# FRDM-MCXN947__Shield_Template.net
KiCad netlist of a schematic drawn in Altium Designer
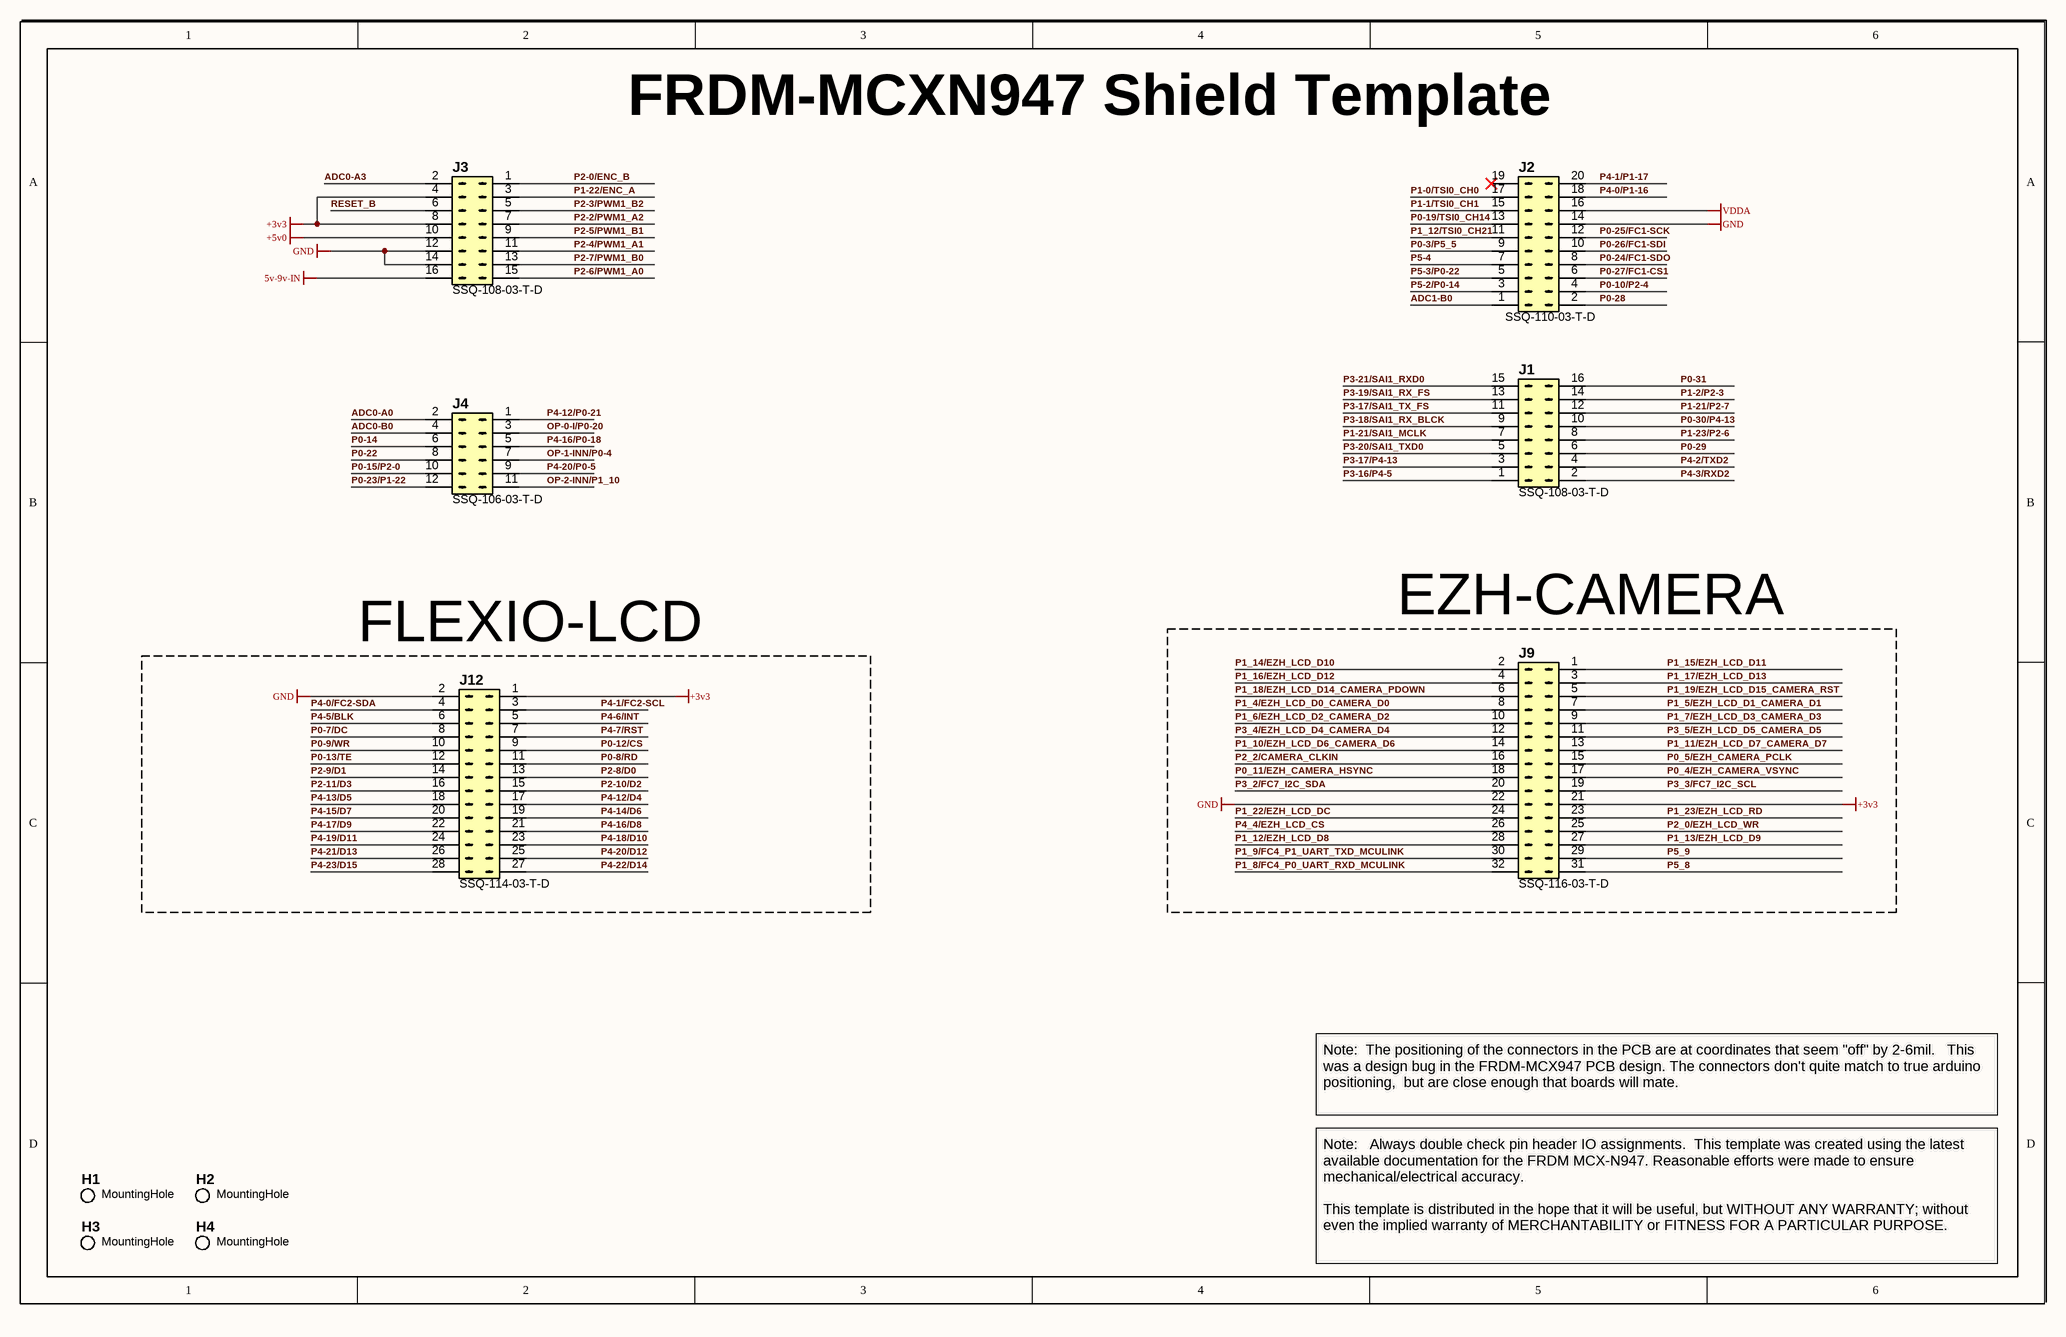
[diagram p0: FRDM-MCXN947__Shield_Template.SchDoc]

(export (version "E")
  (design (tool "Eeschema 10.0.6"))
  (components
    (comp (ref "H1")
      (value "MountingHole")
      (footprint "MountingHole_3.2mm_M3")
      (fields (field (name "Comment") "Mechanical_MountingHole"))
      (libsource (lib "PCB-10012__FRDM-MCXN947__Template__A") (part "Mechanical_MountingHole"))
    )
    (comp (ref "H2")
      (value "MountingHole")
      (footprint "MountingHole_3.2mm_M3")
      (fields (field (name "Comment") "Mechanical_MountingHole"))
      (libsource (lib "PCB-10012__FRDM-MCXN947__Template__A") (part "Mechanical_MountingHole"))
    )
    (comp (ref "H3")
      (value "MountingHole")
      (footprint "MountingHole_3.2mm_M3")
      (fields (field (name "Comment") "Mechanical_MountingHole"))
      (libsource (lib "PCB-10012__FRDM-MCXN947__Template__A") (part "Mechanical_MountingHole"))
    )
    (comp (ref "H4")
      (value "MountingHole")
      (footprint "MountingHole_3.2mm_M3")
      (fields (field (name "Comment") "Mechanical_MountingHole"))
      (libsource (lib "PCB-10012__FRDM-MCXN947__Template__A") (part "Mechanical_MountingHole"))
    )
    (comp (ref "J1")
      (value "SSQ-108-03-T-D")
      (footprint "SSQ-108-03-T-D")
      (fields (field (name "MANUFACTURER") "Samtec Inc."))
      (libsource (lib "") (part "SSQ-108-03-T-D_1"))
    )
    (comp (ref "J2")
      (value "SSQ-110-03-T-D")
      (footprint "SSQ-110-03-T-D")
      (fields
        (field (name "MANUFACTURER") "Samtec Inc.")
        (field (name "MANUFACTURER PART NUMBER") "SSQ-110-23-T-D")
      )
      (libsource (lib "PCB-10012__FRDM-MCXN947__Template__A") (part "SSQ-110-03-T-D"))
    )
    (comp (ref "J3")
      (value "SSQ-108-03-T-D")
      (footprint "SSQ-108-03-T-D")
      (fields (field (name "MANUFACTURER") "Samtec Inc."))
      (libsource (lib "PCB-10012__FRDM-MCXN947__Template__A") (part "SSQ-108-03-T-D"))
    )
    (comp (ref "J4")
      (value "SSQ-106-03-T-D")
      (footprint "SSQ-106-03-T-D")
      (fields (field (name "MANUFACTURER") "Samtec Inc."))
      (libsource (lib "PCB-10012__FRDM-MCXN947__Template__A") (part "SSQ-106-03-T-D"))
    )
    (comp (ref "J9")
      (value "SSQ-116-03-T-D")
      (footprint "SSQ-116-03-T-D")
      (fields (field (name "MANUFACTURER") "Samtec Inc."))
      (libsource (lib "PCB-10012__FRDM-MCXN947__Template__A") (part "SSQ-116-03-T-D"))
    )
    (comp (ref "J12")
      (value "SSQ-114-03-T-D")
      (footprint "SSQ-114-03-T-D")
      (fields (field (name "MANUFACTURER") "Samtec Inc."))
      (libsource (lib "PCB-10012__FRDM-MCXN947__Template__A") (part "SSQ-114-03-T-D"))
    )
  )
  (nets
    (net (code "1") (name "+3v3") (class "Default")
      (node (ref "J12") (pin "1") (pinfunction "Pin_1_1") (pintype "passive"))
      (node (ref "J3") (pin "4") (pinfunction "Pin_4_4") (pintype "passive"))
      (node (ref "J3") (pin "8") (pinfunction "Pin_8_8") (pintype "passive"))
      (node (ref "J9") (pin "21") (pinfunction "Pin_21_21") (pintype "passive"))
    )
    (net (code "2") (name "+5v0") (class "Default")
      (node (ref "J3") (pin "10") (pinfunction "Pin_10_10") (pintype "passive"))
    )
    (net (code "3") (name "/ADC0-A0") (class "Default")
      (node (ref "J4") (pin "2") (pinfunction "Pin_2_2") (pintype "passive"))
    )
    (net (code "4") (name "/ADC0-A3") (class "Default")
      (node (ref "J3") (pin "2") (pinfunction "Pin_2_2") (pintype "passive"))
    )
    (net (code "5") (name "/ADC0-B0") (class "Default")
      (node (ref "J4") (pin "4") (pinfunction "Pin_4_4") (pintype "passive"))
    )
    (net (code "6") (name "/ADC1-B0") (class "Default")
      (node (ref "J2") (pin "1") (pinfunction "Pin_1_1") (pintype "passive"))
    )
    (net (code "7") (name "/OP-0-I{slash}P0-20") (class "Default")
      (node (ref "J4") (pin "3") (pinfunction "Pin_3_3") (pintype "passive"))
    )
    (net (code "8") (name "/OP-1-INN{slash}P0-4") (class "Default")
      (node (ref "J4") (pin "7") (pinfunction "Pin_7_7") (pintype "passive"))
    )
    (net (code "9") (name "/OP-2-INN{slash}P1_10") (class "Default")
      (node (ref "J4") (pin "11") (pinfunction "Pin_11_11") (pintype "passive"))
    )
    (net (code "10") (name "/P0-3{slash}P5_5") (class "Default")
      (node (ref "J2") (pin "9") (pinfunction "Pin_9_9") (pintype "passive"))
    )
    (net (code "11") (name "/P0-7{slash}DC") (class "Default")
      (node (ref "J12") (pin "8") (pinfunction "Pin_8_8") (pintype "passive"))
    )
    (net (code "12") (name "/P0-8{slash}RD") (class "Default")
      (node (ref "J12") (pin "11") (pinfunction "Pin_11_11") (pintype "passive"))
    )
    (net (code "13") (name "/P0-9{slash}WR") (class "Default")
      (node (ref "J12") (pin "10") (pinfunction "Pin_10_10") (pintype "passive"))
    )
    (net (code "14") (name "/P0-10{slash}P2-4") (class "Default")
      (node (ref "J2") (pin "4") (pinfunction "Pin_4_4") (pintype "passive"))
    )
    (net (code "15") (name "/P0-12{slash}CS") (class "Default")
      (node (ref "J12") (pin "9") (pinfunction "Pin_9_9") (pintype "passive"))
    )
    (net (code "16") (name "/P0-13{slash}TE") (class "Default")
      (node (ref "J12") (pin "12") (pinfunction "Pin_12_12") (pintype "passive"))
    )
    (net (code "17") (name "/P0-14") (class "Default")
      (node (ref "J4") (pin "6") (pinfunction "Pin_6_6") (pintype "passive"))
    )
    (net (code "18") (name "/P0-15{slash}P2-0") (class "Default")
      (node (ref "J4") (pin "10") (pinfunction "Pin_10_10") (pintype "passive"))
    )
    (net (code "19") (name "/P0-19{slash}TSI0_CH14") (class "Default")
      (node (ref "J2") (pin "13") (pinfunction "Pin_13_13") (pintype "passive"))
    )
    (net (code "20") (name "/P0-22") (class "Default")
      (node (ref "J4") (pin "8") (pinfunction "Pin_8_8") (pintype "passive"))
    )
    (net (code "21") (name "/P0-23{slash}P1-22") (class "Default")
      (node (ref "J4") (pin "12") (pinfunction "Pin_12_12") (pintype "passive"))
    )
    (net (code "22") (name "/P0-24{slash}FC1-SDO") (class "Default")
      (node (ref "J2") (pin "8") (pinfunction "Pin_8_8") (pintype "passive"))
    )
    (net (code "23") (name "/P0-25{slash}FC1-SCK") (class "Default")
      (node (ref "J2") (pin "12") (pinfunction "Pin_12_12") (pintype "passive"))
    )
    (net (code "24") (name "/P0-26{slash}FC1-SDI") (class "Default")
      (node (ref "J2") (pin "10") (pinfunction "Pin_10_10") (pintype "passive"))
    )
    (net (code "25") (name "/P0-27{slash}FC1-CS1") (class "Default")
      (node (ref "J2") (pin "6") (pinfunction "Pin_6_6") (pintype "passive"))
    )
    (net (code "26") (name "/P0-28") (class "Default")
      (node (ref "J2") (pin "2") (pinfunction "Pin_2_2") (pintype "passive"))
    )
    (net (code "27") (name "/P0-29") (class "Default")
      (node (ref "J1") (pin "6") (pinfunction "Pin_6_6") (pintype "passive"))
    )
    (net (code "28") (name "/P0-30{slash}P4-13") (class "Default")
      (node (ref "J1") (pin "10") (pinfunction "Pin_10_10") (pintype "passive"))
    )
    (net (code "29") (name "/P0-31") (class "Default")
      (node (ref "J1") (pin "16") (pinfunction "Pin_16_16") (pintype "passive"))
    )
    (net (code "30") (name "/P0_4{slash}EZH_CAMERA_VSYNC") (class "Default")
      (node (ref "J9") (pin "17") (pinfunction "Pin_17_17") (pintype "passive"))
    )
    (net (code "31") (name "/P0_5{slash}EZH_CAMERA_PCLK") (class "Default")
      (node (ref "J9") (pin "15") (pinfunction "Pin_15_15") (pintype "passive"))
    )
    (net (code "32") (name "/P0_11{slash}EZH_CAMERA_HSYNC") (class "Default")
      (node (ref "J9") (pin "18") (pinfunction "Pin_18_18") (pintype "passive"))
    )
    (net (code "33") (name "/P1-0{slash}TSI0_CH0") (class "Default")
      (node (ref "J2") (pin "17") (pinfunction "Pin_17_17") (pintype "passive"))
    )
    (net (code "34") (name "/P1-1{slash}TSI0_CH1") (class "Default")
      (node (ref "J2") (pin "15") (pinfunction "Pin_15_15") (pintype "passive"))
    )
    (net (code "35") (name "/P1-2{slash}P2-3") (class "Default")
      (node (ref "J1") (pin "14") (pinfunction "Pin_14_14") (pintype "passive"))
    )
    (net (code "36") (name "/P1-21{slash}P2-7") (class "Default")
      (node (ref "J1") (pin "12") (pinfunction "Pin_12_12") (pintype "passive"))
    )
    (net (code "37") (name "/P1-21{slash}SAI1_MCLK") (class "Default")
      (node (ref "J1") (pin "7") (pinfunction "Pin_7_7") (pintype "passive"))
    )
    (net (code "38") (name "/P1-22{slash}ENC_A") (class "Default")
      (node (ref "J3") (pin "3") (pinfunction "Pin_3_3") (pintype "passive"))
    )
    (net (code "39") (name "/P1-23{slash}P2-6") (class "Default")
      (node (ref "J1") (pin "8") (pinfunction "Pin_8_8") (pintype "passive"))
    )
    (net (code "40") (name "/P1_4{slash}EZH_LCD_D0_CAMERA_D0") (class "Default")
      (node (ref "J9") (pin "8") (pinfunction "Pin_8_8") (pintype "passive"))
    )
    (net (code "41") (name "/P1_5{slash}EZH_LCD_D1_CAMERA_D1") (class "Default")
      (node (ref "J9") (pin "7") (pinfunction "Pin_7_7") (pintype "passive"))
    )
    (net (code "42") (name "/P1_6{slash}EZH_LCD_D2_CAMERA_D2") (class "Default")
      (node (ref "J9") (pin "10") (pinfunction "Pin_10_10") (pintype "passive"))
    )
    (net (code "43") (name "/P1_7{slash}EZH_LCD_D3_CAMERA_D3") (class "Default")
      (node (ref "J9") (pin "9") (pinfunction "Pin_9_9") (pintype "passive"))
    )
    (net (code "44") (name "/P1_8{slash}FC4_P0_UART_RXD_MCULINK") (class "Default")
      (node (ref "J9") (pin "32") (pinfunction "Pin_32_32") (pintype "passive"))
    )
    (net (code "45") (name "/P1_9{slash}FC4_P1_UART_TXD_MCULINK") (class "Default")
      (node (ref "J9") (pin "30") (pinfunction "Pin_30_30") (pintype "passive"))
    )
    (net (code "46") (name "/P1_10{slash}EZH_LCD_D6_CAMERA_D6") (class "Default")
      (node (ref "J9") (pin "14") (pinfunction "Pin_14_14") (pintype "passive"))
    )
    (net (code "47") (name "/P1_11{slash}EZH_LCD_D7_CAMERA_D7") (class "Default")
      (node (ref "J9") (pin "13") (pinfunction "Pin_13_13") (pintype "passive"))
    )
    (net (code "48") (name "/P1_12{slash}EZH_LCD_D8") (class "Default")
      (node (ref "J9") (pin "28") (pinfunction "Pin_28_28") (pintype "passive"))
    )
    (net (code "49") (name "/P1_12{slash}TSI0_CH21") (class "Default")
      (node (ref "J2") (pin "11") (pinfunction "Pin_11_11") (pintype "passive"))
    )
    (net (code "50") (name "/P1_13{slash}EZH_LCD_D9") (class "Default")
      (node (ref "J9") (pin "27") (pinfunction "Pin_27_27") (pintype "passive"))
    )
    (net (code "51") (name "/P1_14{slash}EZH_LCD_D10") (class "Default")
      (node (ref "J9") (pin "2") (pinfunction "Pin_2_2") (pintype "passive"))
    )
    (net (code "52") (name "/P1_15{slash}EZH_LCD_D11") (class "Default")
      (node (ref "J9") (pin "1") (pinfunction "Pin_1_1") (pintype "passive"))
    )
    (net (code "53") (name "/P1_16{slash}EZH_LCD_D12") (class "Default")
      (node (ref "J9") (pin "4") (pinfunction "Pin_4_4") (pintype "passive"))
    )
    (net (code "54") (name "/P1_17{slash}EZH_LCD_D13") (class "Default")
      (node (ref "J9") (pin "3") (pinfunction "Pin_3_3") (pintype "passive"))
    )
    (net (code "55") (name "/P1_18{slash}EZH_LCD_D14_CAMERA_PDOWN") (class "Default")
      (node (ref "J9") (pin "6") (pinfunction "Pin_6_6") (pintype "passive"))
    )
    (net (code "56") (name "/P1_19{slash}EZH_LCD_D15_CAMERA_RST") (class "Default")
      (node (ref "J9") (pin "5") (pinfunction "Pin_5_5") (pintype "passive"))
    )
    (net (code "57") (name "/P1_22{slash}EZH_LCD_DC") (class "Default")
      (node (ref "J9") (pin "24") (pinfunction "Pin_24_24") (pintype "passive"))
    )
    (net (code "58") (name "/P1_23{slash}EZH_LCD_RD") (class "Default")
      (node (ref "J9") (pin "23") (pinfunction "Pin_23_23") (pintype "passive"))
    )
    (net (code "59") (name "/P2-0{slash}ENC_B") (class "Default")
      (node (ref "J3") (pin "1") (pinfunction "Pin_1_1") (pintype "passive"))
    )
    (net (code "60") (name "/P2-2{slash}PWM1_A2") (class "Default")
      (node (ref "J3") (pin "7") (pinfunction "Pin_7_7") (pintype "passive"))
    )
    (net (code "61") (name "/P2-3{slash}PWM1_B2") (class "Default")
      (node (ref "J3") (pin "5") (pinfunction "Pin_5_5") (pintype "passive"))
    )
    (net (code "62") (name "/P2-4{slash}PWM1_A1") (class "Default")
      (node (ref "J3") (pin "11") (pinfunction "Pin_11_11") (pintype "passive"))
    )
    (net (code "63") (name "/P2-5{slash}PWM1_B1") (class "Default")
      (node (ref "J3") (pin "9") (pinfunction "Pin_9_9") (pintype "passive"))
    )
    (net (code "64") (name "/P2-6{slash}PWM1_A0") (class "Default")
      (node (ref "J3") (pin "15") (pinfunction "Pin_15_15") (pintype "passive"))
    )
    (net (code "65") (name "/P2-7{slash}PWM1_B0") (class "Default")
      (node (ref "J3") (pin "13") (pinfunction "Pin_13_13") (pintype "passive"))
    )
    (net (code "66") (name "/P2-8{slash}D0") (class "Default")
      (node (ref "J12") (pin "13") (pinfunction "Pin_13_13") (pintype "passive"))
    )
    (net (code "67") (name "/P2-9{slash}D1") (class "Default")
      (node (ref "J12") (pin "14") (pinfunction "Pin_14_14") (pintype "passive"))
    )
    (net (code "68") (name "/P2-10{slash}D2") (class "Default")
      (node (ref "J12") (pin "15") (pinfunction "Pin_15_15") (pintype "passive"))
    )
    (net (code "69") (name "/P2-11{slash}D3") (class "Default")
      (node (ref "J12") (pin "16") (pinfunction "Pin_16_16") (pintype "passive"))
    )
    (net (code "70") (name "/P2_0{slash}EZH_LCD_WR") (class "Default")
      (node (ref "J9") (pin "25") (pinfunction "Pin_25_25") (pintype "passive"))
    )
    (net (code "71") (name "/P2_2{slash}CAMERA_CLKIN") (class "Default")
      (node (ref "J9") (pin "16") (pinfunction "Pin_16_16") (pintype "passive"))
    )
    (net (code "72") (name "/P3-16{slash}P4-5") (class "Default")
      (node (ref "J1") (pin "1") (pinfunction "Pin_1_1") (pintype "passive"))
    )
    (net (code "73") (name "/P3-17{slash}P4-13") (class "Default")
      (node (ref "J1") (pin "3") (pinfunction "Pin_3_3") (pintype "passive"))
    )
    (net (code "74") (name "/P3-17{slash}SAI1_TX_FS") (class "Default")
      (node (ref "J1") (pin "11") (pinfunction "Pin_11_11") (pintype "passive"))
    )
    (net (code "75") (name "/P3-18{slash}SAI1_RX_BLCK") (class "Default")
      (node (ref "J1") (pin "9") (pinfunction "Pin_9_9") (pintype "passive"))
    )
    (net (code "76") (name "/P3-19{slash}SAI1_RX_FS") (class "Default")
      (node (ref "J1") (pin "13") (pinfunction "Pin_13_13") (pintype "passive"))
    )
    (net (code "77") (name "/P3-20{slash}SAI1_TXD0") (class "Default")
      (node (ref "J1") (pin "5") (pinfunction "Pin_5_5") (pintype "passive"))
    )
    (net (code "78") (name "/P3-21{slash}SAI1_RXD0") (class "Default")
      (node (ref "J1") (pin "15") (pinfunction "Pin_15_15") (pintype "passive"))
    )
    (net (code "79") (name "/P3_2{slash}FC7_I2C_SDA") (class "Default")
      (node (ref "J9") (pin "20") (pinfunction "Pin_20_20") (pintype "passive"))
    )
    (net (code "80") (name "/P3_3{slash}FC7_I2C_SCL") (class "Default")
      (node (ref "J9") (pin "19") (pinfunction "Pin_19_19") (pintype "passive"))
    )
    (net (code "81") (name "/P3_4{slash}EZH_LCD_D4_CAMERA_D4") (class "Default")
      (node (ref "J9") (pin "12") (pinfunction "Pin_12_12") (pintype "passive"))
    )
    (net (code "82") (name "/P3_5{slash}EZH_LCD_D5_CAMERA_D5") (class "Default")
      (node (ref "J9") (pin "11") (pinfunction "Pin_11_11") (pintype "passive"))
    )
    (net (code "83") (name "/P4-0{slash}FC2-SDA") (class "Default")
      (node (ref "J12") (pin "4") (pinfunction "Pin_4_4") (pintype "passive"))
    )
    (net (code "84") (name "/P4-0{slash}P1-16") (class "Default")
      (node (ref "J2") (pin "18") (pinfunction "Pin_18_18") (pintype "passive"))
    )
    (net (code "85") (name "/P4-1{slash}FC2-SCL") (class "Default")
      (node (ref "J12") (pin "3") (pinfunction "Pin_3_3") (pintype "passive"))
    )
    (net (code "86") (name "/P4-1{slash}P1-17") (class "Default")
      (node (ref "J2") (pin "20") (pinfunction "Pin_20_20") (pintype "passive"))
    )
    (net (code "87") (name "/P4-2{slash}TXD2") (class "Default")
      (node (ref "J1") (pin "4") (pinfunction "Pin_4_4") (pintype "passive"))
    )
    (net (code "88") (name "/P4-3{slash}RXD2") (class "Default")
      (node (ref "J1") (pin "2") (pinfunction "Pin_2_2") (pintype "passive"))
    )
    (net (code "89") (name "/P4-5{slash}BLK") (class "Default")
      (node (ref "J12") (pin "6") (pinfunction "Pin_6_6") (pintype "passive"))
    )
    (net (code "90") (name "/P4-6{slash}INT") (class "Default")
      (node (ref "J12") (pin "5") (pinfunction "Pin_5_5") (pintype "passive"))
    )
    (net (code "91") (name "/P4-7{slash}RST") (class "Default")
      (node (ref "J12") (pin "7") (pinfunction "Pin_7_7") (pintype "passive"))
    )
    (net (code "92") (name "/P4-12{slash}D4") (class "Default")
      (node (ref "J12") (pin "17") (pinfunction "Pin_17_17") (pintype "passive"))
    )
    (net (code "93") (name "/P4-12{slash}P0-21") (class "Default")
      (node (ref "J4") (pin "1") (pinfunction "Pin_1_1") (pintype "passive"))
    )
    (net (code "94") (name "/P4-13{slash}D5") (class "Default")
      (node (ref "J12") (pin "18") (pinfunction "Pin_18_18") (pintype "passive"))
    )
    (net (code "95") (name "/P4-14{slash}D6") (class "Default")
      (node (ref "J12") (pin "19") (pinfunction "Pin_19_19") (pintype "passive"))
    )
    (net (code "96") (name "/P4-15{slash}D7") (class "Default")
      (node (ref "J12") (pin "20") (pinfunction "Pin_20_20") (pintype "passive"))
    )
    (net (code "97") (name "/P4-16{slash}D8") (class "Default")
      (node (ref "J12") (pin "21") (pinfunction "Pin_21_21") (pintype "passive"))
    )
    (net (code "98") (name "/P4-16{slash}P0-18") (class "Default")
      (node (ref "J4") (pin "5") (pinfunction "Pin_5_5") (pintype "passive"))
    )
    (net (code "99") (name "/P4-17{slash}D9") (class "Default")
      (node (ref "J12") (pin "22") (pinfunction "Pin_22_22") (pintype "passive"))
    )
    (net (code "100") (name "/P4-18{slash}D10") (class "Default")
      (node (ref "J12") (pin "23") (pinfunction "Pin_23_23") (pintype "passive"))
    )
    (net (code "101") (name "/P4-19{slash}D11") (class "Default")
      (node (ref "J12") (pin "24") (pinfunction "Pin_24_24") (pintype "passive"))
    )
    (net (code "102") (name "/P4-20{slash}D12") (class "Default")
      (node (ref "J12") (pin "25") (pinfunction "Pin_25_25") (pintype "passive"))
    )
    (net (code "103") (name "/P4-20{slash}P0-5") (class "Default")
      (node (ref "J4") (pin "9") (pinfunction "Pin_9_9") (pintype "passive"))
    )
    (net (code "104") (name "/P4-21{slash}D13") (class "Default")
      (node (ref "J12") (pin "26") (pinfunction "Pin_26_26") (pintype "passive"))
    )
    (net (code "105") (name "/P4-22{slash}D14") (class "Default")
      (node (ref "J12") (pin "27") (pinfunction "Pin_27_27") (pintype "passive"))
    )
    (net (code "106") (name "/P4-23{slash}D15") (class "Default")
      (node (ref "J12") (pin "28") (pinfunction "Pin_28_28") (pintype "passive"))
    )
    (net (code "107") (name "/P4_4{slash}EZH_LCD_CS") (class "Default")
      (node (ref "J9") (pin "26") (pinfunction "Pin_26_26") (pintype "passive"))
    )
    (net (code "108") (name "/P5-2{slash}P0-14") (class "Default")
      (node (ref "J2") (pin "3") (pinfunction "Pin_3_3") (pintype "passive"))
    )
    (net (code "109") (name "/P5-3{slash}P0-22") (class "Default")
      (node (ref "J2") (pin "5") (pinfunction "Pin_5_5") (pintype "passive"))
    )
    (net (code "110") (name "/P5-4") (class "Default")
      (node (ref "J2") (pin "7") (pinfunction "Pin_7_7") (pintype "passive"))
    )
    (net (code "111") (name "/P5_8") (class "Default")
      (node (ref "J9") (pin "31") (pinfunction "Pin_31_31") (pintype "passive"))
    )
    (net (code "112") (name "/P5_9") (class "Default")
      (node (ref "J9") (pin "29") (pinfunction "Pin_29_29") (pintype "passive"))
    )
    (net (code "113") (name "/RESET_B") (class "Default")
      (node (ref "J3") (pin "6") (pinfunction "Pin_6_6") (pintype "passive"))
    )
    (net (code "114") (name "5v-9v-IN") (class "Default")
      (node (ref "J3") (pin "16") (pinfunction "Pin_16_16") (pintype "passive"))
    )
    (net (code "115") (name "GND") (class "Default")
      (node (ref "J12") (pin "2") (pinfunction "Pin_2_2") (pintype "passive"))
      (node (ref "J2") (pin "14") (pinfunction "Pin_14_14") (pintype "passive"))
      (node (ref "J3") (pin "12") (pinfunction "Pin_12_12") (pintype "passive"))
      (node (ref "J3") (pin "14") (pinfunction "Pin_14_14") (pintype "passive"))
      (node (ref "J9") (pin "22") (pinfunction "Pin_22_22") (pintype "passive"))
    )
    (net (code "116") (name "VDDA") (class "Default")
      (node (ref "J2") (pin "16") (pinfunction "Pin_16_16") (pintype "passive"))
    )
    (net (code "117") (name "unconnected-(J2-Pin_19-Pad19)") (class "Default")
      (node (ref "J2") (pin "19") (pinfunction "Pin_19_19") (pintype "passive+no_connect"))
    )
  )
)
